# DRV8873S_Breakout.net
KiCad netlist of a schematic drawn in Altium Designer
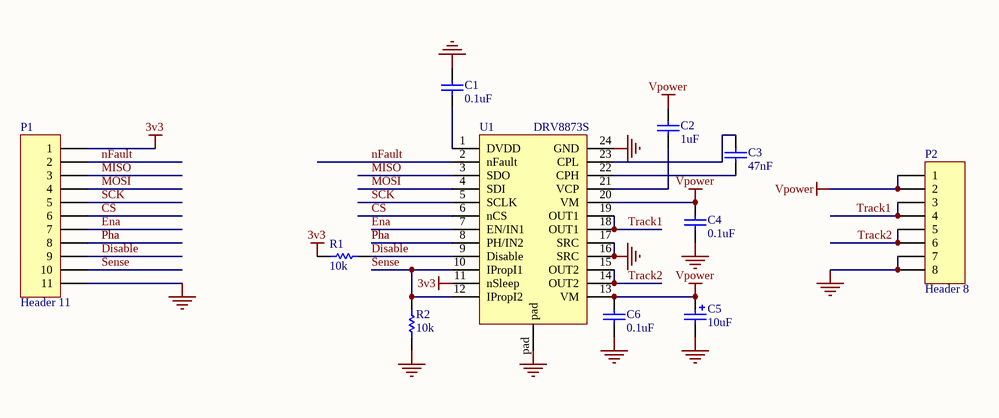
[diagram p0: DRV8873S_Breakout.SchDoc]

(export (version "E")
  (design (tool "Eeschema 10.0.6"))
  (components
    (comp (ref "C1")
      (value "0.1uF")
      (footprint "Cap SMD 0805A")
      (description "Capacitor")
      (fields (field (name "Comment") "Cap") (field (name "PUBLISHER") "Altium Limited"))
      (libsource (lib "Custom") (part "Cap"))
    )
    (comp (ref "C2")
      (value "1uF")
      (footprint "Cap SMD 0805A")
      (description "Capacitor")
      (fields (field (name "Comment") "Cap") (field (name "PUBLISHER") "Altium Limited"))
      (libsource (lib "Custom") (part "Cap"))
    )
    (comp (ref "C3")
      (value "47nF")
      (footprint "Cap SMD 0805A")
      (description "Capacitor")
      (fields (field (name "Comment") "Cap") (field (name "PUBLISHER") "Altium Limited"))
      (libsource (lib "Custom") (part "Cap"))
    )
    (comp (ref "C4")
      (value "0.1uF")
      (footprint "Cap SMD 0805A")
      (description "Capacitor")
      (fields (field (name "Comment") "Cap") (field (name "PUBLISHER") "Altium Limited"))
      (libsource (lib "Custom") (part "Cap"))
    )
    (comp (ref "C5")
      (value "10uF")
      (footprint "Cap SMD Elect 5x5.3")
      (description "Polarized Capacitor (Radial)")
      (fields (field (name "Comment") "Cap Pol") (field (name "PUBLISHER") "Altium Limited"))
      (libsource (lib "Custom") (part "Cap Pol"))
    )
    (comp (ref "C6")
      (value "0.1uF")
      (footprint "Cap SMD 0805A")
      (description "Capacitor")
      (fields (field (name "Comment") "Cap") (field (name "PUBLISHER") "Altium Limited"))
      (libsource (lib "Custom") (part "Cap"))
    )
    (comp (ref "P1")
      (value "Header 11")
      (footprint "HDR1X11")
      (description "Header, 11-Pin")
      (fields (field (name "PUBLISHER") "Altium Limited"))
      (libsource (lib "Miscellaneous Connectors") (part "Header 11"))
    )
    (comp (ref "P2")
      (value "Header 8")
      (footprint "HDR1X8")
      (description "Header, 8-Pin")
      (fields (field (name "PUBLISHER") "Altium Limited"))
      (libsource (lib "Miscellaneous Connectors") (part "Header 8"))
    )
    (comp (ref "R1")
      (value "10k")
      (footprint "Res SMD 0805A")
      (fields (field (name "Comment") "Res1"))
      (libsource (lib "Custom") (part "Resistor"))
    )
    (comp (ref "R2")
      (value "10k")
      (footprint "Res SMD 0805A")
      (fields (field (name "Comment") "Res1"))
      (libsource (lib "Custom") (part "Resistor"))
    )
    (comp (ref "U1")
      (value "DRV8873S")
      (footprint "TSSOP24 PowerPAD")
      (libsource (lib "Custom") (part "DRV8873S"))
    )
  )
  (nets
    (net (code "1") (name "/CS") (class "Default")
      (node (ref "P1") (pin "6") (pinfunction "6_6") (pintype "passive"))
      (node (ref "U1") (pin "6") (pinfunction "nCS_6") (pintype "passive"))
    )
    (net (code "2") (name "/Disable") (class "Default")
      (node (ref "P1") (pin "9") (pinfunction "9_9") (pintype "passive"))
      (node (ref "R1") (pin "1") (pinfunction "1_1") (pintype "passive"))
      (node (ref "U1") (pin "9") (pinfunction "Disable_9") (pintype "passive"))
    )
    (net (code "3") (name "/Ena") (class "Default")
      (node (ref "P1") (pin "7") (pinfunction "7_7") (pintype "passive"))
      (node (ref "U1") (pin "7") (pinfunction "EN/IN1_7") (pintype "passive"))
    )
    (net (code "4") (name "/MISO") (class "Default")
      (node (ref "P1") (pin "3") (pinfunction "3_3") (pintype "passive"))
      (node (ref "U1") (pin "3") (pinfunction "SDO_3") (pintype "passive"))
    )
    (net (code "5") (name "/MOSI") (class "Default")
      (node (ref "P1") (pin "4") (pinfunction "4_4") (pintype "passive"))
      (node (ref "U1") (pin "4") (pinfunction "SDI_4") (pintype "passive"))
    )
    (net (code "6") (name "/Pha") (class "Default")
      (node (ref "P1") (pin "8") (pinfunction "8_8") (pintype "passive"))
      (node (ref "U1") (pin "8") (pinfunction "PH/IN2_8") (pintype "passive"))
    )
    (net (code "7") (name "/SCK") (class "Default")
      (node (ref "P1") (pin "5") (pinfunction "5_5") (pintype "passive"))
      (node (ref "U1") (pin "5") (pinfunction "SCLK_5") (pintype "passive"))
    )
    (net (code "8") (name "/Sense") (class "Default")
      (node (ref "P1") (pin "10") (pinfunction "10_10") (pintype "passive"))
      (node (ref "R2") (pin "2") (pinfunction "2_2") (pintype "passive"))
      (node (ref "U1") (pin "10") (pinfunction "IPropI1_10") (pintype "passive"))
      (node (ref "U1") (pin "12") (pinfunction "IPropI2_12") (pintype "passive"))
    )
    (net (code "9") (name "/Track1") (class "Default")
      (node (ref "P2") (pin "3") (pinfunction "3_3") (pintype "passive"))
      (node (ref "P2") (pin "4") (pinfunction "4_4") (pintype "passive"))
      (node (ref "U1") (pin "18") (pinfunction "OUT1_18") (pintype "passive"))
      (node (ref "U1") (pin "19") (pinfunction "OUT1_19") (pintype "passive"))
    )
    (net (code "10") (name "/Track2") (class "Default")
      (node (ref "P2") (pin "5") (pinfunction "5_5") (pintype "passive"))
      (node (ref "P2") (pin "6") (pinfunction "6_6") (pintype "passive"))
      (node (ref "U1") (pin "14") (pinfunction "OUT2_14") (pintype "passive"))
      (node (ref "U1") (pin "15") (pinfunction "OUT2_15") (pintype "passive"))
    )
    (net (code "11") (name "/nFault") (class "Default")
      (node (ref "P1") (pin "2") (pinfunction "2_2") (pintype "passive"))
      (node (ref "U1") (pin "2") (pinfunction "nFault_2") (pintype "passive"))
    )
    (net (code "12") (name "3v3") (class "Default")
      (node (ref "P1") (pin "1") (pinfunction "1_1") (pintype "passive"))
      (node (ref "R1") (pin "2") (pinfunction "2_2") (pintype "passive"))
      (node (ref "U1") (pin "11") (pinfunction "nSleep_11") (pintype "passive"))
    )
    (net (code "13") (name "GND") (class "Default")
      (node (ref "C1") (pin "1") (pinfunction "1_1") (pintype "passive"))
      (node (ref "C4") (pin "1") (pinfunction "1_1") (pintype "passive"))
      (node (ref "C5") (pin "2") (pinfunction "2_2") (pintype "passive"))
      (node (ref "C6") (pin "1") (pinfunction "1_1") (pintype "passive"))
      (node (ref "P1") (pin "11") (pinfunction "11_11") (pintype "passive"))
      (node (ref "P2") (pin "7") (pinfunction "7_7") (pintype "passive"))
      (node (ref "P2") (pin "8") (pinfunction "8_8") (pintype "passive"))
      (node (ref "R2") (pin "1") (pinfunction "1_1") (pintype "passive"))
      (node (ref "U1") (pin "16") (pinfunction "SRC_16") (pintype "passive"))
      (node (ref "U1") (pin "17") (pinfunction "SRC_17") (pintype "passive"))
      (node (ref "U1") (pin "24") (pinfunction "GND_24") (pintype "passive"))
      (node (ref "U1") (pin "pad") (pinfunction "pad_pad") (pintype "passive"))
    )
    (net (code "14") (name "Net-(U1-CPH)") (class "Default")
      (node (ref "C3") (pin "1") (pinfunction "1_1") (pintype "passive"))
      (node (ref "U1") (pin "22") (pinfunction "CPH_22") (pintype "passive"))
    )
    (net (code "15") (name "Net-(U1-CPL)") (class "Default")
      (node (ref "C3") (pin "2") (pinfunction "2_2") (pintype "passive"))
      (node (ref "U1") (pin "23") (pinfunction "CPL_23") (pintype "passive"))
    )
    (net (code "16") (name "Net-(U1-DVDD)") (class "Default")
      (node (ref "C1") (pin "2") (pinfunction "2_2") (pintype "passive"))
      (node (ref "U1") (pin "1") (pinfunction "DVDD_1") (pintype "passive"))
    )
    (net (code "17") (name "Net-(U1-VCP)") (class "Default")
      (node (ref "C2") (pin "1") (pinfunction "1_1") (pintype "passive"))
      (node (ref "U1") (pin "21") (pinfunction "VCP_21") (pintype "passive"))
    )
    (net (code "18") (name "Vpower") (class "Default")
      (node (ref "C2") (pin "2") (pinfunction "2_2") (pintype "passive"))
      (node (ref "C4") (pin "2") (pinfunction "2_2") (pintype "passive"))
      (node (ref "C5") (pin "1") (pinfunction "1_1") (pintype "passive"))
      (node (ref "C6") (pin "2") (pinfunction "2_2") (pintype "passive"))
      (node (ref "P2") (pin "1") (pinfunction "1_1") (pintype "passive"))
      (node (ref "P2") (pin "2") (pinfunction "2_2") (pintype "passive"))
      (node (ref "U1") (pin "13") (pinfunction "VM_13") (pintype "passive"))
      (node (ref "U1") (pin "20") (pinfunction "VM_20") (pintype "passive"))
    )
  )
)
